# Adafruit_DS2484_I2C_to_1-Wire_Breakout.net
KiCad netlist of a schematic drawn in EAGLE
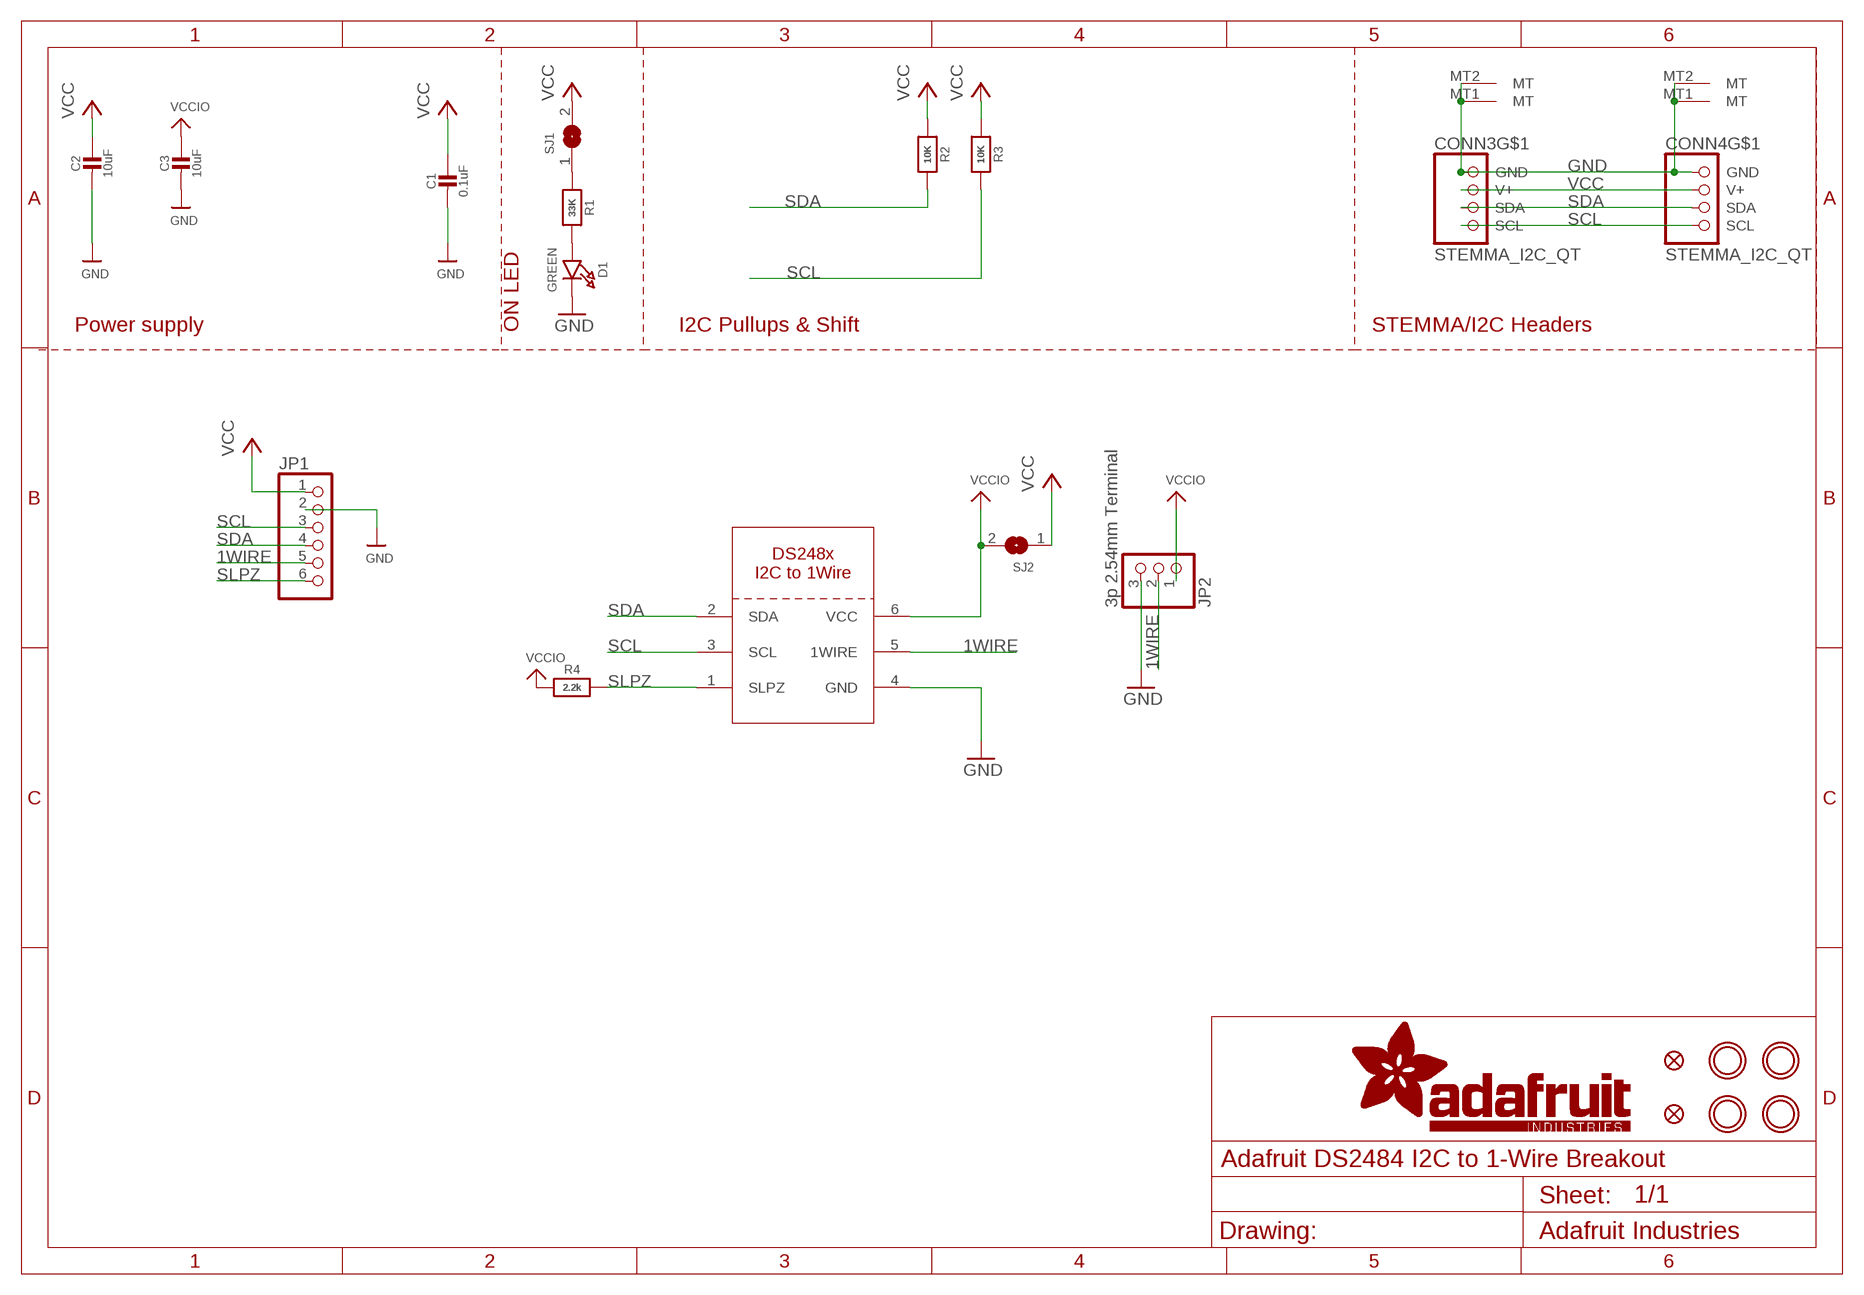
[diagram p0: schematic, sheet 1]

(export (version "E")
  (design (tool "Eeschema 10.0.6"))
  (components
    (comp (ref "C1")
      (value "0.1uF")
      (footprint "eagle-import:0603-NO")
      (libsource (lib "eagle-import") (part "CAP_CERAMIC0603_NO"))
    )
    (comp (ref "C2")
      (value "10uF")
      (footprint "eagle-import:0805-NO")
      (libsource (lib "eagle-import") (part "CAP_CERAMIC0805-NOOUTLINE"))
    )
    (comp (ref "C3")
      (value "10uF")
      (footprint "eagle-import:0805-NO")
      (libsource (lib "eagle-import") (part "CAP_CERAMIC0805-NOOUTLINE"))
    )
    (comp (ref "CONN3")
      (value "STEMMA_I2C_QT")
      (footprint "eagle-import:JST_SH4")
      (libsource (lib "eagle-import") (part "STEMMA_I2C_QT"))
    )
    (comp (ref "CONN4")
      (value "STEMMA_I2C_QT")
      (footprint "eagle-import:JST_SH4")
      (libsource (lib "eagle-import") (part "STEMMA_I2C_QT"))
    )
    (comp (ref "D1")
      (value "GREEN")
      (footprint "eagle-import:CHIPLED_0603_NOOUTLINE")
      (libsource (lib "eagle-import") (part "LED0603_NOOUTLINE"))
    )
    (comp (ref "FID3")
      (value "FIDUCIAL_0.5MM")
      (footprint "eagle-import:FIDUCIAL_0.5MM")
      (libsource (lib "eagle-import") (part "FIDUCIAL_0.5MM"))
    )
    (comp (ref "FID4")
      (value "FIDUCIAL_0.5MM")
      (footprint "eagle-import:FIDUCIAL_0.5MM")
      (libsource (lib "eagle-import") (part "FIDUCIAL_0.5MM"))
    )
    (comp (ref "IC1")
      (value "DS248XR")
      (footprint "eagle-import:SOT23-6")
      (libsource (lib "eagle-import") (part "DS248XR"))
    )
    (comp (ref "JP1")
      (value "HEADER-1X670MIL")
      (footprint "eagle-import:1X06_ROUND_70")
      (libsource (lib "eagle-import") (part "HEADER-1X670MIL"))
    )
    (comp (ref "JP2")
      (value "3p 2.54mm Terminal")
      (footprint "eagle-import:1X03_2.54MMTERMINAL")
      (libsource (lib "eagle-import") (part "HEADER-1X3_254TERM"))
    )
    (comp (ref "R1")
      (value "33K")
      (footprint "eagle-import:0603-NO")
      (libsource (lib "eagle-import") (part "RESISTOR_0603_NOOUT"))
    )
    (comp (ref "R2")
      (value "10K")
      (footprint "eagle-import:0603-NO")
      (libsource (lib "eagle-import") (part "RESISTOR_0603_NOOUT"))
    )
    (comp (ref "R3")
      (value "10K")
      (footprint "eagle-import:0603-NO")
      (libsource (lib "eagle-import") (part "RESISTOR_0603_NOOUT"))
    )
    (comp (ref "R4")
      (value "2.2k")
      (footprint "eagle-import:0603-NO")
      (libsource (lib "eagle-import") (part "RESISTOR_0603_NOOUT"))
    )
    (comp (ref "SJ1")
      (value "SOLDERJUMPERCLOSED")
      (footprint "eagle-import:SOLDERJUMPER_CLOSEDWIRE")
      (libsource (lib "eagle-import") (part "SOLDERJUMPERCLOSED"))
    )
    (comp (ref "SJ2")
      (value "SOLDERJUMPERCLOSED")
      (footprint "eagle-import:SOLDERJUMPER_CLOSEDWIRE")
      (libsource (lib "eagle-import") (part "SOLDERJUMPERCLOSED"))
    )
    (comp (ref "U$1")
      (value "MOUNTINGHOLE2.5")
      (footprint "eagle-import:MOUNTINGHOLE_2.5_PLATED")
      (libsource (lib "eagle-import") (part "MOUNTINGHOLE2.5"))
    )
    (comp (ref "U$17")
      (value "MOUNTINGHOLE2.5")
      (footprint "eagle-import:MOUNTINGHOLE_2.5_PLATED")
      (libsource (lib "eagle-import") (part "MOUNTINGHOLE2.5"))
    )
    (comp (ref "U$19")
      (value "MOUNTINGHOLE2.5")
      (footprint "eagle-import:MOUNTINGHOLE_2.5_PLATED")
      (libsource (lib "eagle-import") (part "MOUNTINGHOLE2.5"))
    )
    (comp (ref "U$21")
      (value "MOUNTINGHOLE2.5")
      (footprint "eagle-import:MOUNTINGHOLE_2.5_PLATED")
      (libsource (lib "eagle-import") (part "MOUNTINGHOLE2.5"))
    )
  )
  (nets
    (net (code "1") (name "/1WIRE") (class "Default")
      (node (ref "IC1") (pin "5") (pinfunction "1WIRE_5") (pintype "bidirectional"))
      (node (ref "JP1") (pin "5") (pinfunction "5_5") (pintype "passive"))
      (node (ref "JP2") (pin "2") (pinfunction "2_2") (pintype "passive"))
    )
    (net (code "2") (name "/SCL") (class "Default")
      (node (ref "CONN3") (pin "4") (pinfunction "SCL_4") (pintype "passive"))
      (node (ref "CONN4") (pin "4") (pinfunction "SCL_4") (pintype "passive"))
      (node (ref "IC1") (pin "3") (pinfunction "SCL_3") (pintype "bidirectional"))
      (node (ref "JP1") (pin "3") (pinfunction "3_3") (pintype "passive"))
      (node (ref "R3") (pin "2") (pinfunction "2_2") (pintype "passive"))
    )
    (net (code "3") (name "/SDA") (class "Default")
      (node (ref "CONN3") (pin "3") (pinfunction "SDA_3") (pintype "passive"))
      (node (ref "CONN4") (pin "3") (pinfunction "SDA_3") (pintype "passive"))
      (node (ref "IC1") (pin "2") (pinfunction "SDA_2") (pintype "bidirectional"))
      (node (ref "JP1") (pin "4") (pinfunction "4_4") (pintype "passive"))
      (node (ref "R2") (pin "2") (pinfunction "2_2") (pintype "passive"))
    )
    (net (code "4") (name "/SLPZ") (class "Default")
      (node (ref "IC1") (pin "1") (pinfunction "SLPZ_1") (pintype "input"))
      (node (ref "JP1") (pin "6") (pinfunction "6_6") (pintype "passive"))
      (node (ref "R4") (pin "2") (pinfunction "2_2") (pintype "passive"))
    )
    (net (code "5") (name "GND") (class "Default")
      (node (ref "C1") (pin "2") (pinfunction "2_2") (pintype "passive"))
      (node (ref "C2") (pin "2") (pinfunction "2_2") (pintype "passive"))
      (node (ref "C3") (pin "2") (pinfunction "2_2") (pintype "passive"))
      (node (ref "CONN3") (pin "1") (pinfunction "GND_1") (pintype "passive"))
      (node (ref "CONN3") (pin "MT1") (pinfunction "MT_MT1") (pintype "bidirectional"))
      (node (ref "CONN3") (pin "MT2") (pinfunction "MT_MT2") (pintype "bidirectional"))
      (node (ref "CONN4") (pin "1") (pinfunction "GND_1") (pintype "passive"))
      (node (ref "CONN4") (pin "MT1") (pinfunction "MT_MT1") (pintype "bidirectional"))
      (node (ref "CONN4") (pin "MT2") (pinfunction "MT_MT2") (pintype "bidirectional"))
      (node (ref "D1") (pin "C") (pinfunction "C_C") (pintype "passive"))
      (node (ref "IC1") (pin "4") (pinfunction "GND_4") (pintype "power_in"))
      (node (ref "JP1") (pin "2") (pinfunction "2_2") (pintype "passive"))
      (node (ref "JP2") (pin "3") (pinfunction "3_3") (pintype "passive"))
    )
    (net (code "6") (name "Net-(D1-PadA)") (class "Default")
      (node (ref "D1") (pin "A") (pinfunction "A_A") (pintype "passive"))
      (node (ref "R1") (pin "2") (pinfunction "2_2") (pintype "passive"))
    )
    (net (code "7") (name "Net-(R1-Pad1)") (class "Default")
      (node (ref "R1") (pin "1") (pinfunction "1_1") (pintype "passive"))
      (node (ref "SJ1") (pin "1") (pinfunction "1_1") (pintype "passive"))
    )
    (net (code "8") (name "VCC") (class "Default")
      (node (ref "C1") (pin "1") (pinfunction "1_1") (pintype "passive"))
      (node (ref "C2") (pin "1") (pinfunction "1_1") (pintype "passive"))
      (node (ref "CONN3") (pin "2") (pinfunction "V+_2") (pintype "passive"))
      (node (ref "CONN4") (pin "2") (pinfunction "V+_2") (pintype "passive"))
      (node (ref "JP1") (pin "1") (pinfunction "1_1") (pintype "passive"))
      (node (ref "R2") (pin "1") (pinfunction "1_1") (pintype "passive"))
      (node (ref "R3") (pin "1") (pinfunction "1_1") (pintype "passive"))
      (node (ref "SJ1") (pin "2") (pinfunction "2_2") (pintype "passive"))
      (node (ref "SJ2") (pin "1") (pinfunction "1_1") (pintype "passive"))
    )
    (net (code "9") (name "VCCIO") (class "Default")
      (node (ref "C3") (pin "1") (pinfunction "1_1") (pintype "passive"))
      (node (ref "IC1") (pin "6") (pinfunction "VCC_6") (pintype "power_in"))
      (node (ref "JP2") (pin "1") (pinfunction "1_1") (pintype "passive"))
      (node (ref "R4") (pin "1") (pinfunction "1_1") (pintype "passive"))
      (node (ref "SJ2") (pin "2") (pinfunction "2_2") (pintype "passive"))
    )
  )
)
